# TCAN330_PINOUT.net
KiCad netlist of a schematic drawn in Altium Designer
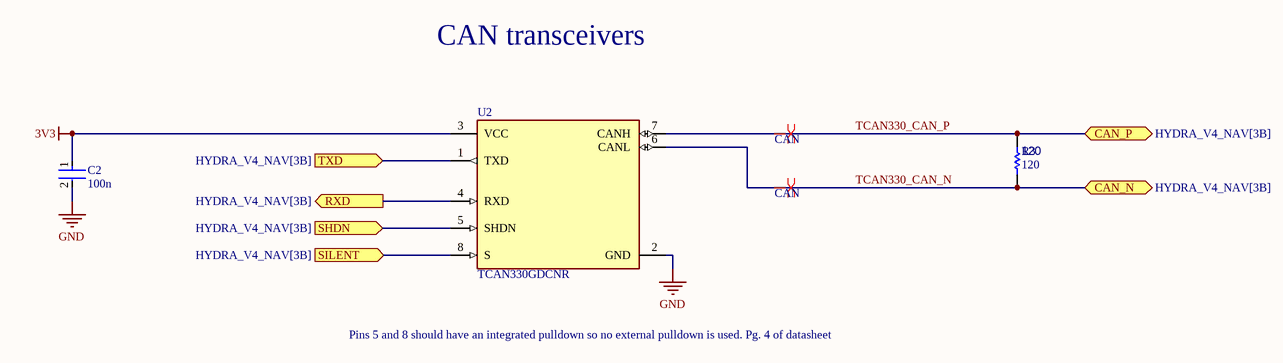
[diagram p0: TCAN330_PINOUT.SchDoc]

(export (version "E")
  (design (tool "Eeschema 10.0.6"))
  (components
    (comp (ref "C2")
      (value "100n")
      (footprint "FP-0402-L_1_0_0_05-W_0_5-IPC_A")
      (description "LARGE PADS, 0402 CAP, CHANGE COMMENT TO MATCH REAL P/N")
      (libsource (lib "Space Concordia") (part "b4654b650e69147ec39a6b967a45e02"))
    )
    (comp (ref "R3")
      (value "120")
      (footprint "R0603B")
      (description "Resistor")
      (fields (field (name "ALTIUM_VALUE") "120"))
      (libsource (lib "Space Concordia") (part "Resistor"))
    )
    (comp (ref "U2")
      (value "TCAN330GDCNR")
      (footprint "FP-DCN0008A-MFG")
      (description "IC TRANSCEIVER 1/1 SOT23-8")
      (libsource (lib "Altium Content Vault") (part "22681b49c22ad38c6a4e12e04c36c7a"))
    )
  )
  (nets
    (net (code "1") (name "/RXD") (class "Default")
      (node (ref "U2") (pin "4") (pinfunction "RXD_4") (pintype "input"))
    )
    (net (code "2") (name "/SHDN") (class "Default")
      (node (ref "U2") (pin "5") (pinfunction "SHDN_5") (pintype "input"))
    )
    (net (code "3") (name "/SILENT") (class "Default")
      (node (ref "U2") (pin "8") (pinfunction "S_8") (pintype "input"))
    )
    (net (code "4") (name "/TCAN330_CAN_N") (class "Default")
      (node (ref "R3") (pin "1") (pinfunction "1_1") (pintype "passive"))
      (node (ref "U2") (pin "6") (pinfunction "CANL_6") (pintype "bidirectional"))
    )
    (net (code "5") (name "/TCAN330_CAN_P") (class "Default")
      (node (ref "R3") (pin "2") (pinfunction "2_2") (pintype "passive"))
      (node (ref "U2") (pin "7") (pinfunction "CANH_7") (pintype "bidirectional"))
    )
    (net (code "6") (name "/TXD") (class "Default")
      (node (ref "U2") (pin "1") (pinfunction "TXD_1") (pintype "output"))
    )
    (net (code "7") (name "3V3") (class "Default")
      (node (ref "C2") (pin "1") (pinfunction "1_1") (pintype "passive"))
      (node (ref "U2") (pin "3") (pinfunction "VCC_3") (pintype "power_in"))
    )
    (net (code "8") (name "GND") (class "Default")
      (node (ref "C2") (pin "2") (pinfunction "2_2") (pintype "passive"))
      (node (ref "U2") (pin "2") (pinfunction "GND_2") (pintype "power_in"))
    )
  )
)
